# MUDE_V2.net
KiCad netlist of a schematic drawn in EAGLE
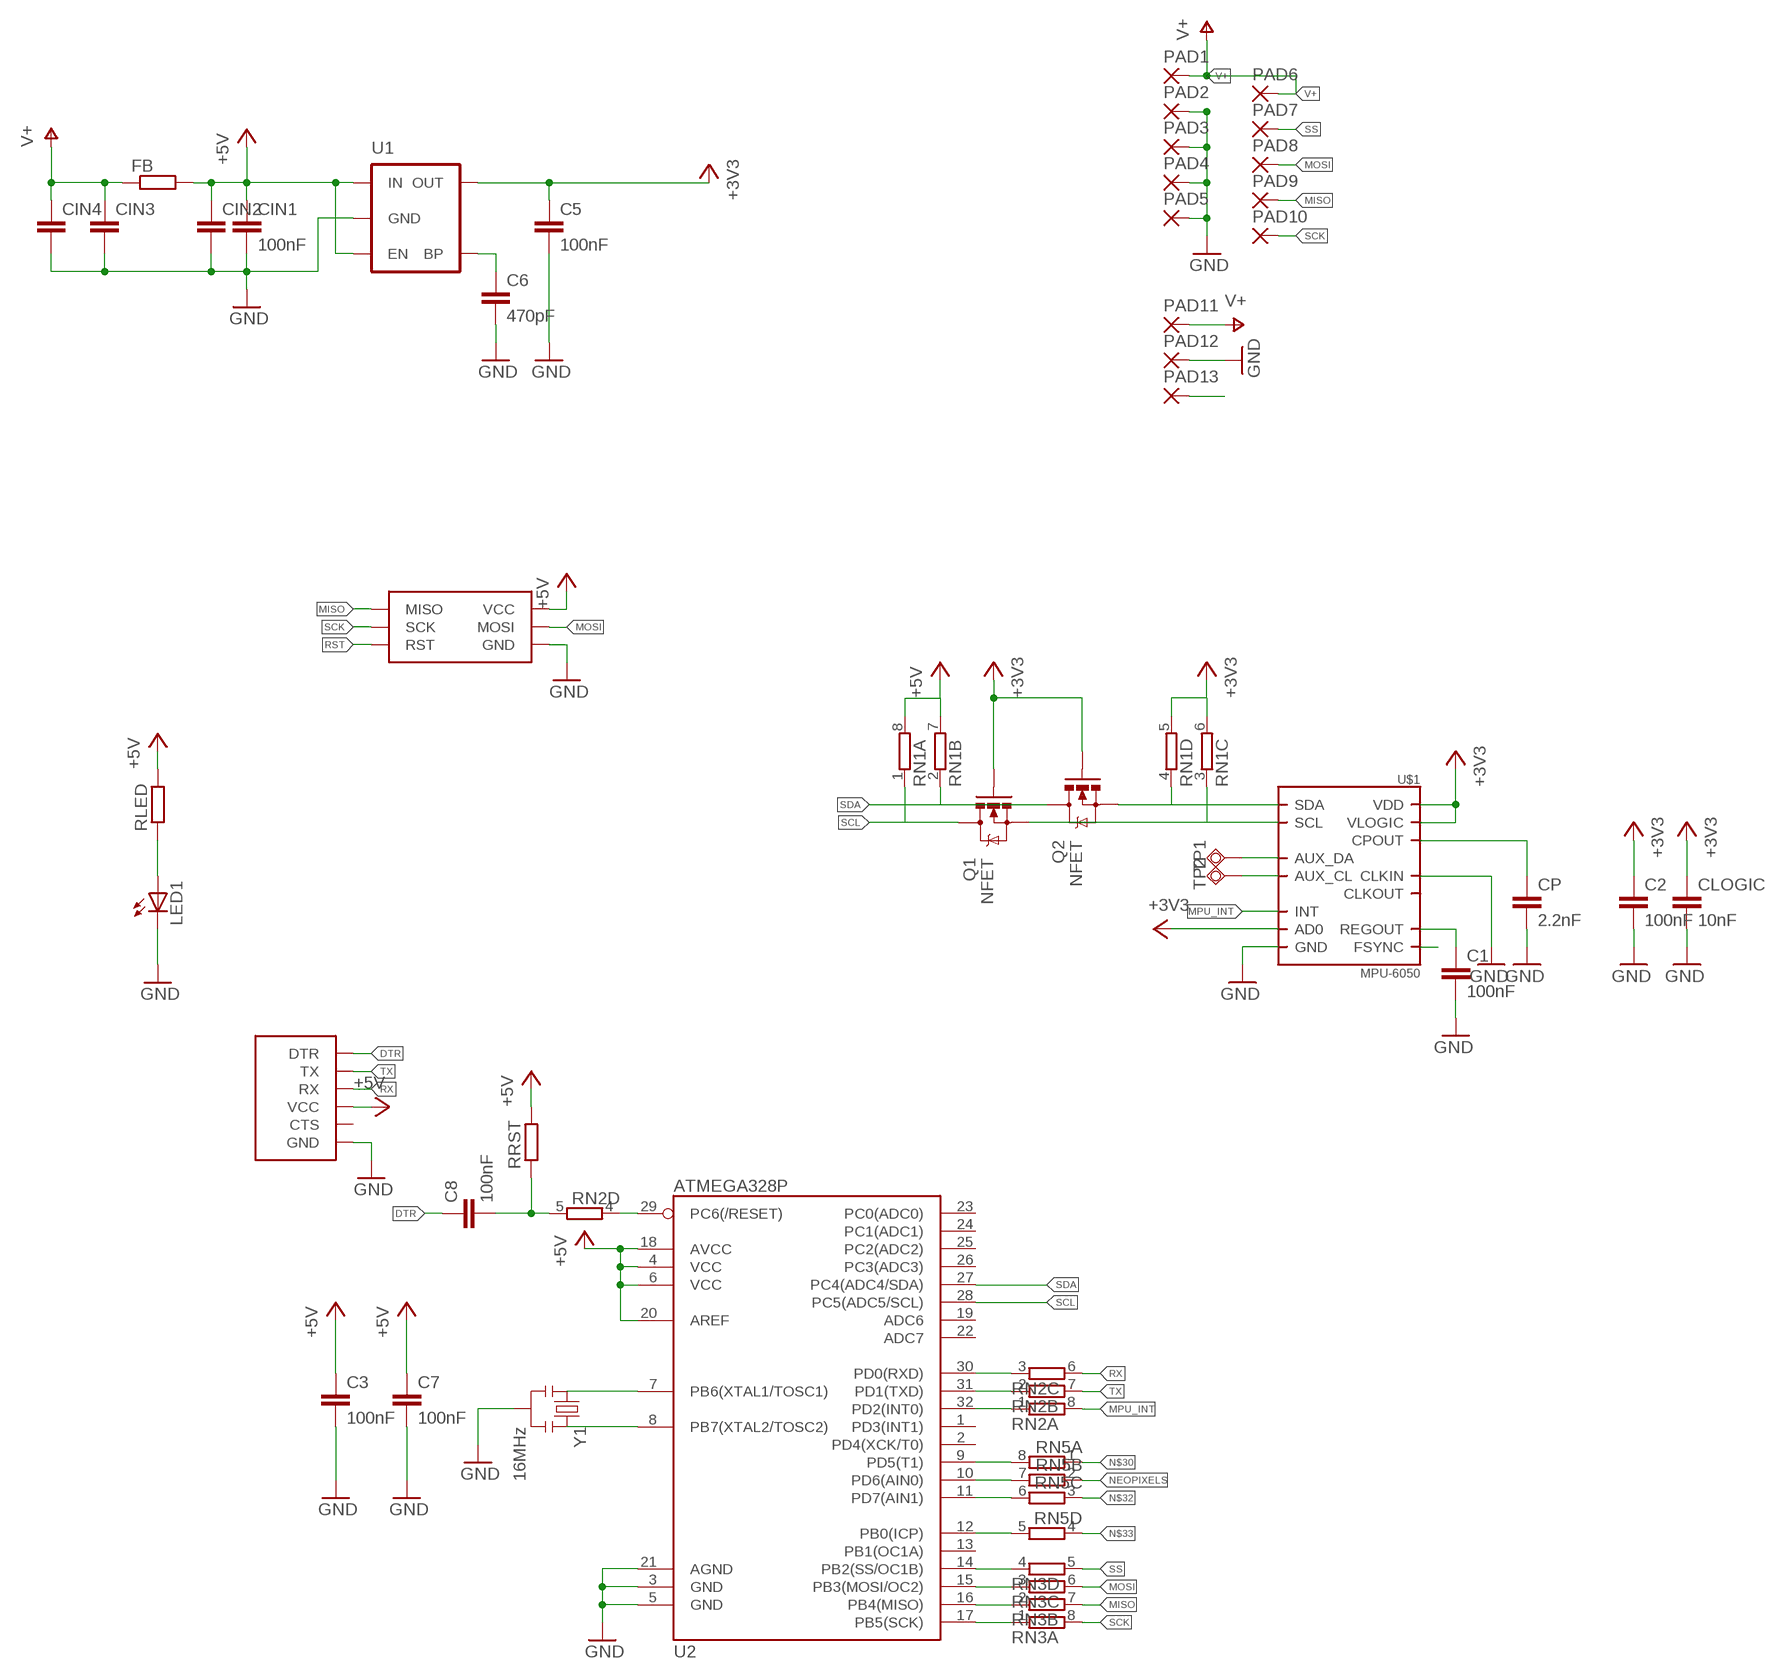
[diagram p0: schematic, sheet 1]

(export (version "E")
  (design (tool "Eeschema 10.0.6"))
  (components
    (comp (ref "C1")
      (value "100nF")
      (footprint "eagle-import:C0603")
      (libsource (lib "eagle-import") (part "C-EUC0603"))
    )
    (comp (ref "C2")
      (value "100nF")
      (footprint "eagle-import:C0603")
      (libsource (lib "eagle-import") (part "C-EUC0603"))
    )
    (comp (ref "C3")
      (value "100nF")
      (footprint "eagle-import:C0603")
      (libsource (lib "eagle-import") (part "C-EUC0603"))
    )
    (comp (ref "C5")
      (value "100nF")
      (footprint "eagle-import:C0805")
      (libsource (lib "eagle-import") (part "C-EUC0805"))
    )
    (comp (ref "C6")
      (value "470pF")
      (footprint "eagle-import:C0603")
      (libsource (lib "eagle-import") (part "C-EUC0603"))
    )
    (comp (ref "C7")
      (value "100nF")
      (footprint "eagle-import:C0603")
      (libsource (lib "eagle-import") (part "C-EUC0603"))
    )
    (comp (ref "C8")
      (value "100nF")
      (footprint "eagle-import:C0603")
      (libsource (lib "eagle-import") (part "C-EUC0603"))
    )
    (comp (ref "CIN1")
      (value "100nF")
      (footprint "eagle-import:C0603")
      (libsource (lib "eagle-import") (part "C-EUC0603"))
    )
    (comp (ref "CIN2")
      (value "C-EUC0805")
      (footprint "eagle-import:C0805")
      (libsource (lib "eagle-import") (part "C-EUC0805"))
    )
    (comp (ref "CIN3")
      (value "C-EUC1210")
      (footprint "eagle-import:C1210")
      (libsource (lib "eagle-import") (part "C-EUC1210"))
    )
    (comp (ref "CIN4")
      (value "C-EUC1210")
      (footprint "eagle-import:C1210")
      (libsource (lib "eagle-import") (part "C-EUC1210"))
    )
    (comp (ref "CLOGIC")
      (value "10nF")
      (footprint "eagle-import:C0603")
      (libsource (lib "eagle-import") (part "C-EUC0603"))
    )
    (comp (ref "CP")
      (value "2.2nF")
      (footprint "eagle-import:C0603")
      (libsource (lib "eagle-import") (part "C-EUC0603"))
    )
    (comp (ref "FB")
      (value "R-EU_R0603")
      (footprint "eagle-import:R0603")
      (libsource (lib "eagle-import") (part "R-EU_R0603"))
    )
    (comp (ref "LED1")
      (value "LED0603")
      (footprint "eagle-import:LED-0603")
      (libsource (lib "eagle-import") (part "LED0603"))
    )
    (comp (ref "PAD1")
      (value "SMD2")
      (footprint "eagle-import:SMD1,27-2,54")
      (libsource (lib "eagle-import") (part "SMD2"))
    )
    (comp (ref "PAD2")
      (value "SMD2")
      (footprint "eagle-import:SMD1,27-2,54")
      (libsource (lib "eagle-import") (part "SMD2"))
    )
    (comp (ref "PAD3")
      (value "SMD2")
      (footprint "eagle-import:SMD1,27-2,54")
      (libsource (lib "eagle-import") (part "SMD2"))
    )
    (comp (ref "PAD4")
      (value "SMD2")
      (footprint "eagle-import:SMD1,27-2,54")
      (libsource (lib "eagle-import") (part "SMD2"))
    )
    (comp (ref "PAD5")
      (value "SMD2")
      (footprint "eagle-import:SMD1,27-2,54")
      (libsource (lib "eagle-import") (part "SMD2"))
    )
    (comp (ref "PAD6")
      (value "SMD2")
      (footprint "eagle-import:SMD1,27-2,54")
      (libsource (lib "eagle-import") (part "SMD2"))
    )
    (comp (ref "PAD7")
      (value "SMD2")
      (footprint "eagle-import:SMD1,27-2,54")
      (libsource (lib "eagle-import") (part "SMD2"))
    )
    (comp (ref "PAD8")
      (value "SMD2")
      (footprint "eagle-import:SMD1,27-2,54")
      (libsource (lib "eagle-import") (part "SMD2"))
    )
    (comp (ref "PAD9")
      (value "SMD2")
      (footprint "eagle-import:SMD1,27-2,54")
      (libsource (lib "eagle-import") (part "SMD2"))
    )
    (comp (ref "PAD10")
      (value "SMD2")
      (footprint "eagle-import:SMD1,27-2,54")
      (libsource (lib "eagle-import") (part "SMD2"))
    )
    (comp (ref "PAD11")
      (value "SMD2")
      (footprint "eagle-import:SMD1,27-2,54")
      (libsource (lib "eagle-import") (part "SMD2"))
    )
    (comp (ref "PAD12")
      (value "SMD2")
      (footprint "eagle-import:SMD1,27-2,54")
      (libsource (lib "eagle-import") (part "SMD2"))
    )
    (comp (ref "PAD13")
      (value "SMD2")
      (footprint "eagle-import:SMD1,27-2,54")
      (libsource (lib "eagle-import") (part "SMD2"))
    )
    (comp (ref "Q1")
      (value "NFET")
      (footprint "eagle-import:SOT23")
      (libsource (lib "eagle-import") (part "MOSFET-NCHANNELBSS123LT1G"))
    )
    (comp (ref "Q2")
      (value "NFET")
      (footprint "eagle-import:SOT23")
      (libsource (lib "eagle-import") (part "MOSFET-NCHANNELBSS123LT1G"))
    )
    (comp (ref "RLED")
      (value "R-EU_R0603")
      (footprint "eagle-import:R0603")
      (libsource (lib "eagle-import") (part "R-EU_R0603"))
    )
    (comp (ref "RN1")
      (value "4R-N0603-ARV")
      (footprint "eagle-import:0603-ARV")
      (libsource (lib "eagle-import") (part "4R-N0603-ARV"))
    )
    (comp (ref "RN2")
      (value "4R-N0603-ARV")
      (footprint "eagle-import:0603-ARV")
      (libsource (lib "eagle-import") (part "4R-N0603-ARV"))
    )
    (comp (ref "RN3")
      (value "4R-N0603-ARV")
      (footprint "eagle-import:0603-ARV")
      (libsource (lib "eagle-import") (part "4R-N0603-ARV"))
    )
    (comp (ref "RN5")
      (value "4R-N0603-ARV")
      (footprint "eagle-import:0603-ARV")
      (libsource (lib "eagle-import") (part "4R-N0603-ARV"))
    )
    (comp (ref "RRST")
      (value "R-EU_R0603")
      (footprint "eagle-import:R0603")
      (libsource (lib "eagle-import") (part "R-EU_R0603"))
    )
    (comp (ref "TP1")
      (value "TPSQTP10R")
      (footprint "eagle-import:TP10R")
      (libsource (lib "eagle-import") (part "TPSQTP10R"))
    )
    (comp (ref "TP2")
      (value "TPSQTP10R")
      (footprint "eagle-import:TP10R")
      (libsource (lib "eagle-import") (part "TPSQTP10R"))
    )
    (comp (ref "U$1")
      (value "MPU-6050")
      (footprint "eagle-import:QFN.24.4X4")
      (libsource (lib "eagle-import") (part "MPU-6050"))
    )
    (comp (ref "U$2")
      (value "FTDI_HEADERSMD")
      (footprint "eagle-import:FTDI_HEADER_SMD")
      (libsource (lib "eagle-import") (part "FTDI_HEADERSMD"))
    )
    (comp (ref "U$3")
      (value "ISP_POGOISP_POGO")
      (footprint "eagle-import:ISP_POGO")
      (libsource (lib "eagle-import") (part "ISP_POGOISP_POGO"))
    )
    (comp (ref "U1")
      (value "MIC52053.3V")
      (footprint "eagle-import:SOT23-5")
      (libsource (lib "eagle-import") (part "MIC52053.3V"))
    )
    (comp (ref "U2")
      (value "ATMEGA328P")
      (footprint "eagle-import:TQFP32-08")
      (libsource (lib "eagle-import") (part "ATMEGA328_SMT"))
    )
    (comp (ref "Y1")
      (value "16MHz")
      (footprint "eagle-import:RESONATOR-SMD")
      (libsource (lib "eagle-import") (part "RESONATOR16MHZ"))
    )
  )
  (nets
    (net (code "1") (name "+3V3") (class "Default")
      (node (ref "C2") (pin "1") (pinfunction "1_1") (pintype "passive"))
      (node (ref "C5") (pin "1") (pinfunction "1_1") (pintype "passive"))
      (node (ref "CLOGIC") (pin "1") (pinfunction "1_1") (pintype "passive"))
      (node (ref "Q1") (pin "1") (pinfunction "G_1") (pintype "passive"))
      (node (ref "Q2") (pin "1") (pinfunction "G_1") (pintype "passive"))
      (node (ref "RN1") (pin "5") (pinfunction "2_5") (pintype "passive"))
      (node (ref "RN1") (pin "6") (pinfunction "2_6") (pintype "passive"))
      (node (ref "U$1") (pin "13") (pinfunction "VDD_13") (pintype "bidirectional"))
      (node (ref "U$1") (pin "8") (pinfunction "VLOGIC_8") (pintype "bidirectional"))
      (node (ref "U$1") (pin "9") (pinfunction "AD0_9") (pintype "bidirectional"))
      (node (ref "U1") (pin "5") (pinfunction "OUT_5") (pintype "passive"))
    )
    (net (code "2") (name "+5V") (class "Default")
      (node (ref "C3") (pin "1") (pinfunction "1_1") (pintype "passive"))
      (node (ref "C7") (pin "1") (pinfunction "1_1") (pintype "passive"))
      (node (ref "CIN1") (pin "1") (pinfunction "1_1") (pintype "passive"))
      (node (ref "CIN2") (pin "1") (pinfunction "1_1") (pintype "passive"))
      (node (ref "FB") (pin "2") (pinfunction "2_2") (pintype "passive"))
      (node (ref "RLED") (pin "2") (pinfunction "2_2") (pintype "passive"))
      (node (ref "RN1") (pin "7") (pinfunction "2_7") (pintype "passive"))
      (node (ref "RN1") (pin "8") (pinfunction "2_8") (pintype "passive"))
      (node (ref "RRST") (pin "2") (pinfunction "2_2") (pintype "passive"))
      (node (ref "U$2") (pin "VCC") (pinfunction "VCC_VCC") (pintype "bidirectional"))
      (node (ref "U$3") (pin "VCC") (pinfunction "VCC_VCC") (pintype "bidirectional"))
      (node (ref "U1") (pin "1") (pinfunction "IN_1") (pintype "input"))
      (node (ref "U1") (pin "3") (pinfunction "EN_3") (pintype "input"))
      (node (ref "U2") (pin "18") (pinfunction "AVCC_18") (pintype "bidirectional"))
      (node (ref "U2") (pin "20") (pinfunction "AREF_20") (pintype "bidirectional"))
      (node (ref "U2") (pin "4") (pinfunction "VCC_4") (pintype "bidirectional"))
      (node (ref "U2") (pin "6") (pinfunction "VCC_6") (pintype "bidirectional"))
    )
    (net (code "3") (name "DTR") (class "Default")
      (node (ref "C8") (pin "1") (pinfunction "1_1") (pintype "passive"))
      (node (ref "U$2") (pin "DTR") (pinfunction "DTR_DTR") (pintype "bidirectional"))
    )
    (net (code "4") (name "GND") (class "Default")
      (node (ref "C1") (pin "2") (pinfunction "2_2") (pintype "passive"))
      (node (ref "C2") (pin "2") (pinfunction "2_2") (pintype "passive"))
      (node (ref "C3") (pin "2") (pinfunction "2_2") (pintype "passive"))
      (node (ref "C5") (pin "2") (pinfunction "2_2") (pintype "passive"))
      (node (ref "C6") (pin "2") (pinfunction "2_2") (pintype "passive"))
      (node (ref "C7") (pin "2") (pinfunction "2_2") (pintype "passive"))
      (node (ref "CIN1") (pin "2") (pinfunction "2_2") (pintype "passive"))
      (node (ref "CIN2") (pin "2") (pinfunction "2_2") (pintype "passive"))
      (node (ref "CIN3") (pin "2") (pinfunction "2_2") (pintype "passive"))
      (node (ref "CIN4") (pin "2") (pinfunction "2_2") (pintype "passive"))
      (node (ref "CLOGIC") (pin "2") (pinfunction "2_2") (pintype "passive"))
      (node (ref "CP") (pin "2") (pinfunction "2_2") (pintype "passive"))
      (node (ref "LED1") (pin "C") (pinfunction "C_C") (pintype "passive"))
      (node (ref "PAD12") (pin "1") (pinfunction "P_1") (pintype "passive"))
      (node (ref "PAD2") (pin "1") (pinfunction "P_1") (pintype "passive"))
      (node (ref "PAD3") (pin "1") (pinfunction "P_1") (pintype "passive"))
      (node (ref "PAD4") (pin "1") (pinfunction "P_1") (pintype "passive"))
      (node (ref "PAD5") (pin "1") (pinfunction "P_1") (pintype "passive"))
      (node (ref "U$1") (pin "1") (pinfunction "CLKIN_1") (pintype "bidirectional"))
      (node (ref "U$1") (pin "18") (pinfunction "GND_18") (pintype "bidirectional"))
      (node (ref "U$2") (pin "GND") (pinfunction "GND_GND") (pintype "bidirectional"))
      (node (ref "U$3") (pin "GND") (pinfunction "GND_GND") (pintype "bidirectional"))
      (node (ref "U1") (pin "2") (pinfunction "GND_2") (pintype "input"))
      (node (ref "U2") (pin "21") (pinfunction "AGND_21") (pintype "bidirectional"))
      (node (ref "U2") (pin "3") (pinfunction "GND_3") (pintype "bidirectional"))
      (node (ref "U2") (pin "5") (pinfunction "GND_5") (pintype "bidirectional"))
      (node (ref "Y1") (pin "2") (pinfunction "2_2") (pintype "passive"))
    )
    (net (code "5") (name "MISO") (class "Default")
      (node (ref "PAD9") (pin "1") (pinfunction "P_1") (pintype "passive"))
      (node (ref "RN3") (pin "7") (pinfunction "2_7") (pintype "passive"))
      (node (ref "U$3") (pin "MISO") (pinfunction "MISO_MISO") (pintype "bidirectional"))
    )
    (net (code "6") (name "MOSI") (class "Default")
      (node (ref "PAD8") (pin "1") (pinfunction "P_1") (pintype "passive"))
      (node (ref "RN3") (pin "6") (pinfunction "2_6") (pintype "passive"))
      (node (ref "U$3") (pin "MOSI") (pinfunction "MOSI_MOSI") (pintype "bidirectional"))
    )
    (net (code "7") (name "MPU_INT") (class "Default")
      (node (ref "RN2") (pin "8") (pinfunction "2_8") (pintype "passive"))
      (node (ref "U$1") (pin "12") (pinfunction "INT_12") (pintype "bidirectional"))
    )
    (net (code "8") (name "N$30") (class "Default")
      (node (ref "RN5") (pin "1") (pinfunction "1_1") (pintype "passive"))
    )
    (net (code "9") (name "N$32") (class "Default")
      (node (ref "RN5") (pin "3") (pinfunction "1_3") (pintype "passive"))
    )
    (net (code "10") (name "N$33") (class "Default")
      (node (ref "RN5") (pin "4") (pinfunction "1_4") (pintype "passive"))
    )
    (net (code "11") (name "NEOPIXELS") (class "Default")
      (node (ref "PAD13") (pin "1") (pinfunction "P_1") (pintype "passive"))
      (node (ref "RN5") (pin "2") (pinfunction "1_2") (pintype "passive"))
    )
    (net (code "12") (name "Net-(LED1-PadA)") (class "Default")
      (node (ref "LED1") (pin "A") (pinfunction "A_A") (pintype "passive"))
      (node (ref "RLED") (pin "1") (pinfunction "1_1") (pintype "passive"))
    )
    (net (code "13") (name "Net-(Q1-S)") (class "Default")
      (node (ref "Q1") (pin "2") (pinfunction "S_2") (pintype "passive"))
      (node (ref "RN1") (pin "3") (pinfunction "1_3") (pintype "passive"))
      (node (ref "U$1") (pin "23") (pinfunction "SCL_23") (pintype "bidirectional"))
    )
    (net (code "14") (name "Net-(Q2-S)") (class "Default")
      (node (ref "Q2") (pin "2") (pinfunction "S_2") (pintype "passive"))
      (node (ref "RN1") (pin "4") (pinfunction "1_4") (pintype "passive"))
      (node (ref "U$1") (pin "24") (pinfunction "SDA_24") (pintype "bidirectional"))
    )
    (net (code "15") (name "Net-(RN2B-1)") (class "Default")
      (node (ref "RN2") (pin "2") (pinfunction "1_2") (pintype "passive"))
      (node (ref "U2") (pin "31") (pinfunction "PD1(TXD)_31") (pintype "bidirectional"))
    )
    (net (code "16") (name "Net-(RN2C-1)") (class "Default")
      (node (ref "RN2") (pin "3") (pinfunction "1_3") (pintype "passive"))
      (node (ref "U2") (pin "30") (pinfunction "PD0(RXD)_30") (pintype "bidirectional"))
    )
    (net (code "17") (name "Net-(RN2D-1)") (class "Default")
      (node (ref "RN2") (pin "4") (pinfunction "1_4") (pintype "passive"))
      (node (ref "U2") (pin "29") (pinfunction "PC6(/RESET)_29") (pintype "bidirectional"))
    )
    (net (code "18") (name "Net-(RN2D-2)") (class "Default")
      (node (ref "C8") (pin "2") (pinfunction "2_2") (pintype "passive"))
      (node (ref "RN2") (pin "5") (pinfunction "2_5") (pintype "passive"))
      (node (ref "RRST") (pin "1") (pinfunction "1_1") (pintype "passive"))
    )
    (net (code "19") (name "Net-(RN3B-1)") (class "Default")
      (node (ref "RN3") (pin "2") (pinfunction "1_2") (pintype "passive"))
      (node (ref "U2") (pin "16") (pinfunction "PB4(MISO)_16") (pintype "bidirectional"))
    )
    (net (code "20") (name "Net-(RN3C-1)") (class "Default")
      (node (ref "RN3") (pin "3") (pinfunction "1_3") (pintype "passive"))
      (node (ref "U2") (pin "15") (pinfunction "PB3(MOSI/OC2)_15") (pintype "bidirectional"))
    )
    (net (code "21") (name "Net-(RN3D-1)") (class "Default")
      (node (ref "RN3") (pin "4") (pinfunction "1_4") (pintype "passive"))
      (node (ref "U2") (pin "14") (pinfunction "PB2(SS/OC1B)_14") (pintype "bidirectional"))
    )
    (net (code "22") (name "Net-(RN5A-2)") (class "Default")
      (node (ref "RN5") (pin "8") (pinfunction "2_8") (pintype "passive"))
      (node (ref "U2") (pin "9") (pinfunction "PD5(T1)_9") (pintype "bidirectional"))
    )
    (net (code "23") (name "Net-(RN5B-2)") (class "Default")
      (node (ref "RN5") (pin "7") (pinfunction "2_7") (pintype "passive"))
      (node (ref "U2") (pin "10") (pinfunction "PD6(AIN0)_10") (pintype "bidirectional"))
    )
    (net (code "24") (name "Net-(RN5C-2)") (class "Default")
      (node (ref "RN5") (pin "6") (pinfunction "2_6") (pintype "passive"))
      (node (ref "U2") (pin "11") (pinfunction "PD7(AIN1)_11") (pintype "bidirectional"))
    )
    (net (code "25") (name "Net-(RN5D-2)") (class "Default")
      (node (ref "RN5") (pin "5") (pinfunction "2_5") (pintype "passive"))
      (node (ref "U2") (pin "12") (pinfunction "PB0(ICP)_12") (pintype "bidirectional"))
    )
    (net (code "26") (name "Net-(U$1-AUX_CL)") (class "Default")
      (node (ref "TP2") (pin "TP") (pinfunction "TP_TP") (pintype "input"))
      (node (ref "U$1") (pin "7") (pinfunction "AUX_CL_7") (pintype "bidirectional"))
    )
    (net (code "27") (name "Net-(U$1-AUX_DA)") (class "Default")
      (node (ref "TP1") (pin "TP") (pinfunction "TP_TP") (pintype "input"))
      (node (ref "U$1") (pin "6") (pinfunction "AUX_DA_6") (pintype "bidirectional"))
    )
    (net (code "28") (name "Net-(U$1-CPOUT)") (class "Default")
      (node (ref "CP") (pin "1") (pinfunction "1_1") (pintype "passive"))
      (node (ref "U$1") (pin "20") (pinfunction "CPOUT_20") (pintype "bidirectional"))
    )
    (net (code "29") (name "Net-(U$1-REGOUT)") (class "Default")
      (node (ref "C1") (pin "1") (pinfunction "1_1") (pintype "passive"))
      (node (ref "U$1") (pin "10") (pinfunction "REGOUT_10") (pintype "bidirectional"))
    )
    (net (code "30") (name "Net-(U1-BP)") (class "Default")
      (node (ref "C6") (pin "1") (pinfunction "1_1") (pintype "passive"))
      (node (ref "U1") (pin "4") (pinfunction "BP_4") (pintype "input"))
    )
    (net (code "31") (name "Net-(U2-PB5(SCK))") (class "Default")
      (node (ref "RN3") (pin "1") (pinfunction "1_1") (pintype "passive"))
      (node (ref "U2") (pin "17") (pinfunction "PB5(SCK)_17") (pintype "bidirectional"))
    )
    (net (code "32") (name "Net-(U2-PB6(XTAL1{slash}TOSC1))") (class "Default")
      (node (ref "U2") (pin "7") (pinfunction "PB6(XTAL1/TOSC1)_7") (pintype "bidirectional"))
      (node (ref "Y1") (pin "1") (pinfunction "1_1") (pintype "passive"))
    )
    (net (code "33") (name "Net-(U2-PB7(XTAL2{slash}TOSC2))") (class "Default")
      (node (ref "U2") (pin "8") (pinfunction "PB7(XTAL2/TOSC2)_8") (pintype "bidirectional"))
      (node (ref "Y1") (pin "3") (pinfunction "3_3") (pintype "passive"))
    )
    (net (code "34") (name "Net-(U2-PD2(INT0))") (class "Default")
      (node (ref "RN2") (pin "1") (pinfunction "1_1") (pintype "passive"))
      (node (ref "U2") (pin "32") (pinfunction "PD2(INT0)_32") (pintype "bidirectional"))
    )
    (net (code "35") (name "RST") (class "Default")
      (node (ref "U$3") (pin "RST") (pinfunction "RST_RST") (pintype "bidirectional"))
    )
    (net (code "36") (name "RX") (class "Default")
      (node (ref "RN2") (pin "6") (pinfunction "2_6") (pintype "passive"))
      (node (ref "U$2") (pin "RX") (pinfunction "RX_RX") (pintype "bidirectional"))
    )
    (net (code "37") (name "SCK") (class "Default")
      (node (ref "PAD10") (pin "1") (pinfunction "P_1") (pintype "passive"))
      (node (ref "RN3") (pin "8") (pinfunction "2_8") (pintype "passive"))
      (node (ref "U$3") (pin "SCK") (pinfunction "SCK_SCK") (pintype "bidirectional"))
    )
    (net (code "38") (name "SCL") (class "Default")
      (node (ref "Q1") (pin "3") (pinfunction "D_3") (pintype "passive"))
      (node (ref "RN1") (pin "1") (pinfunction "1_1") (pintype "passive"))
      (node (ref "U2") (pin "28") (pinfunction "PC5(ADC5/SCL)_28") (pintype "bidirectional"))
    )
    (net (code "39") (name "SDA") (class "Default")
      (node (ref "Q2") (pin "3") (pinfunction "D_3") (pintype "passive"))
      (node (ref "RN1") (pin "2") (pinfunction "1_2") (pintype "passive"))
      (node (ref "U2") (pin "27") (pinfunction "PC4(ADC4/SDA)_27") (pintype "bidirectional"))
    )
    (net (code "40") (name "SS") (class "Default")
      (node (ref "PAD7") (pin "1") (pinfunction "P_1") (pintype "passive"))
      (node (ref "RN3") (pin "5") (pinfunction "2_5") (pintype "passive"))
    )
    (net (code "41") (name "TX") (class "Default")
      (node (ref "RN2") (pin "7") (pinfunction "2_7") (pintype "passive"))
      (node (ref "U$2") (pin "TX") (pinfunction "TX_TX") (pintype "bidirectional"))
    )
    (net (code "42") (name "V+") (class "Default")
      (node (ref "CIN3") (pin "1") (pinfunction "1_1") (pintype "passive"))
      (node (ref "CIN4") (pin "1") (pinfunction "1_1") (pintype "passive"))
      (node (ref "FB") (pin "1") (pinfunction "1_1") (pintype "passive"))
      (node (ref "PAD1") (pin "1") (pinfunction "P_1") (pintype "passive"))
      (node (ref "PAD11") (pin "1") (pinfunction "P_1") (pintype "passive"))
      (node (ref "PAD6") (pin "1") (pinfunction "P_1") (pintype "passive"))
    )
    (net (code "43") (name "unconnected-(U$1-CLKOUT-Pad22)") (class "Default")
      (node (ref "U$1") (pin "22") (pinfunction "CLKOUT_22") (pintype "bidirectional"))
    )
    (net (code "44") (name "unconnected-(U$1-FSYNC-Pad11)") (class "Default")
      (node (ref "U$1") (pin "11") (pinfunction "FSYNC_11") (pintype "bidirectional"))
    )
    (net (code "45") (name "unconnected-(U$2-PadCTS)") (class "Default")
      (node (ref "U$2") (pin "CTS") (pinfunction "CTS_CTS") (pintype "bidirectional"))
    )
    (net (code "46") (name "unconnected-(U2-ADC6-Pad19)") (class "Default")
      (node (ref "U2") (pin "19") (pinfunction "ADC6_19") (pintype "bidirectional"))
    )
    (net (code "47") (name "unconnected-(U2-ADC7-Pad22)") (class "Default")
      (node (ref "U2") (pin "22") (pinfunction "ADC7_22") (pintype "bidirectional"))
    )
    (net (code "48") (name "unconnected-(U2-PB1(OC1A)-Pad13)") (class "Default")
      (node (ref "U2") (pin "13") (pinfunction "PB1(OC1A)_13") (pintype "bidirectional"))
    )
    (net (code "49") (name "unconnected-(U2-PC0(ADC0)-Pad23)") (class "Default")
      (node (ref "U2") (pin "23") (pinfunction "PC0(ADC0)_23") (pintype "bidirectional"))
    )
    (net (code "50") (name "unconnected-(U2-PC1(ADC1)-Pad24)") (class "Default")
      (node (ref "U2") (pin "24") (pinfunction "PC1(ADC1)_24") (pintype "bidirectional"))
    )
    (net (code "51") (name "unconnected-(U2-PC2(ADC2)-Pad25)") (class "Default")
      (node (ref "U2") (pin "25") (pinfunction "PC2(ADC2)_25") (pintype "bidirectional"))
    )
    (net (code "52") (name "unconnected-(U2-PC3(ADC3)-Pad26)") (class "Default")
      (node (ref "U2") (pin "26") (pinfunction "PC3(ADC3)_26") (pintype "bidirectional"))
    )
    (net (code "53") (name "unconnected-(U2-PD3(INT1)-Pad1)") (class "Default")
      (node (ref "U2") (pin "1") (pinfunction "PD3(INT1)_1") (pintype "bidirectional"))
    )
    (net (code "54") (name "unconnected-(U2-PD4(XCK{slash}T0)-Pad2)") (class "Default")
      (node (ref "U2") (pin "2") (pinfunction "PD4(XCK/T0)_2") (pintype "bidirectional"))
    )
  )
)
